# Microcontroller.net
KiCad netlist of a schematic drawn in Altium Designer
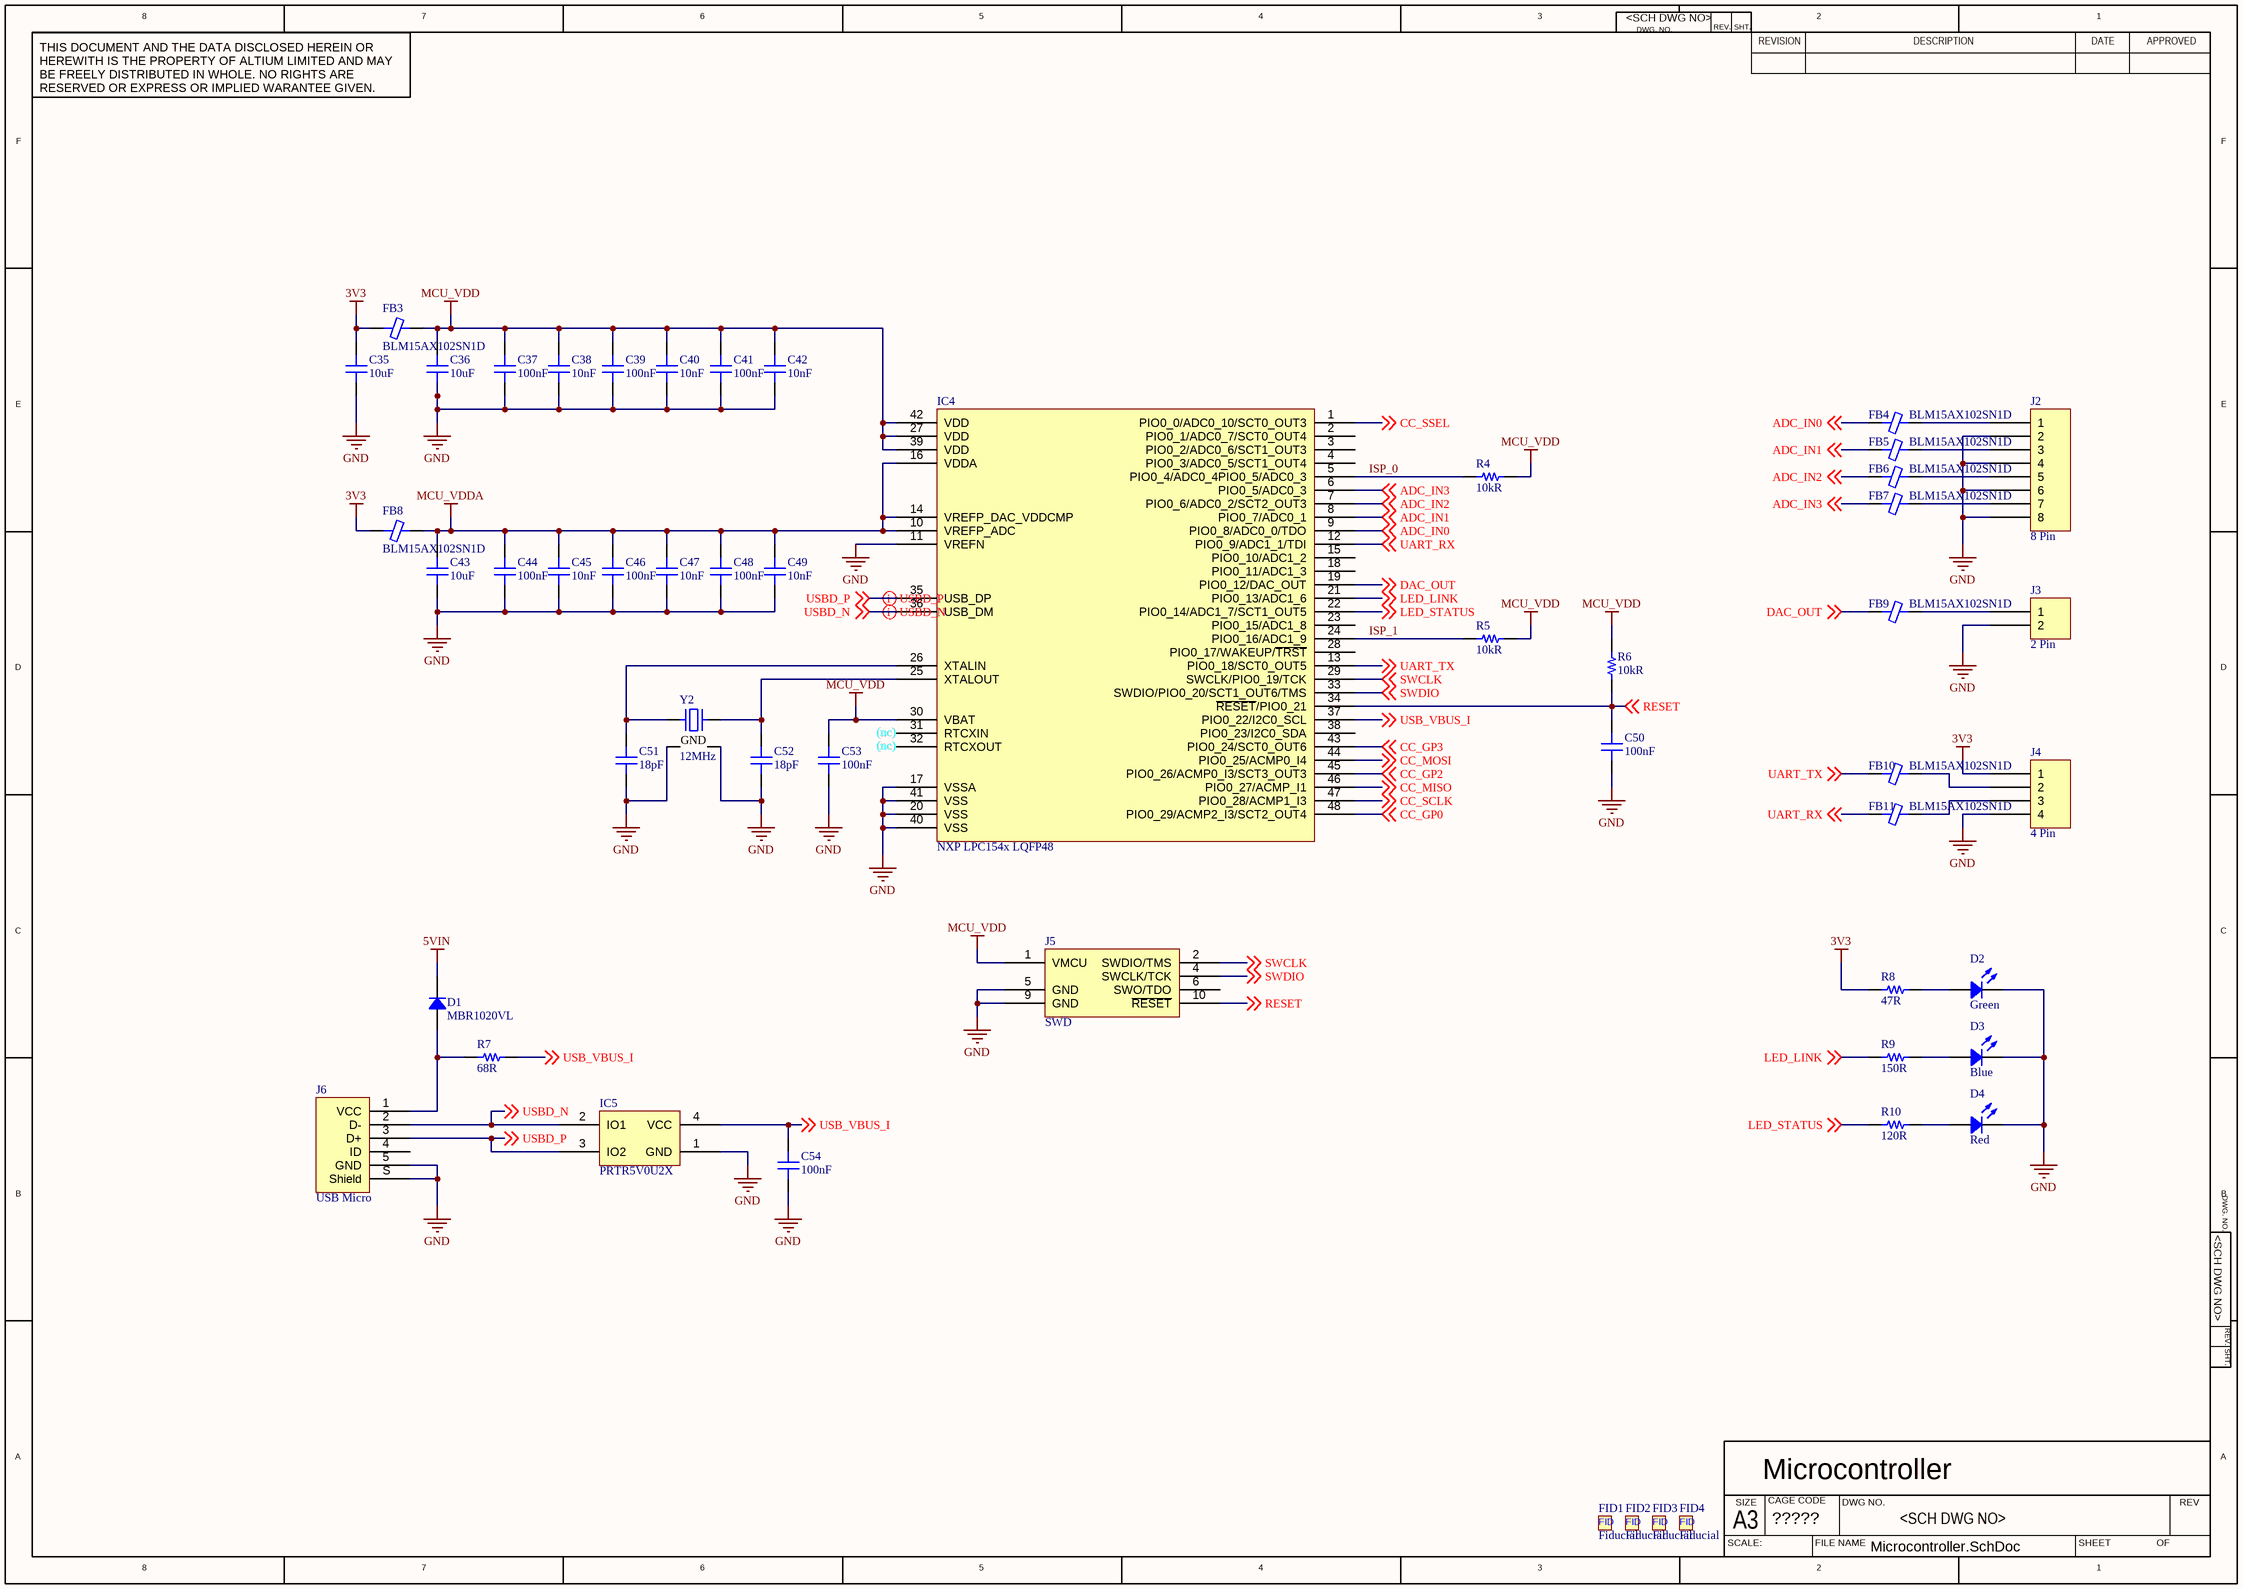
[diagram p0: Microcontroller.SchDoc]

(export (version "E")
  (design (tool "Eeschema 10.0.6"))
  (components
    (comp (ref "C35")
      (value "10uF")
      (footprint "CAP 0805/2012")
      (description "Cap Ceramic 10uF 10V X5R 10% SMD 0805 85C Embossed T/R")
      (fields (field (name "TOLERANCE") "10%") (field (name "VOLTAGE") "10V"))
      (libsource (lib "SCH - PASSIVES - CAPACITOR") (part "Capacitor"))
    )
    (comp (ref "C36")
      (value "10uF")
      (footprint "CAP 0805/2012")
      (description "Cap Ceramic 10uF 10V X5R 10% SMD 0805 85C Embossed T/R")
      (fields (field (name "TOLERANCE") "10%") (field (name "VOLTAGE") "10V"))
      (libsource (lib "SCH - PASSIVES - CAPACITOR") (part "Capacitor"))
    )
    (comp (ref "C37")
      (value "100nF")
      (footprint "CAP 0402/1005")
      (description "Cap Ceramic 0.1uF 10V X5R 20% Pad SMD 0402 85C T/R")
      (fields (field (name "TOLERANCE") "20%"))
      (libsource (lib "SCH - PASSIVES - CAPACITOR") (part "Capacitor"))
    )
    (comp (ref "C38")
      (value "10nF")
      (footprint "CAP 0402/1005")
      (description "TAIYO YUDEN - TMK105B7103KV-F - CERAMIC CAPACITOR 0.01UF, 25V, X7R, 10%, 0402, FULL REEL")
      (fields (field (name "TOLERANCE") "10%") (field (name "VOLTAGE") "25V"))
      (libsource (lib "SCH - PASSIVES - CAPACITOR") (part "Capacitor"))
    )
    (comp (ref "C39")
      (value "100nF")
      (footprint "CAP 0402/1005")
      (description "Cap Ceramic 0.1uF 10V X5R 20% Pad SMD 0402 85C T/R")
      (fields (field (name "TOLERANCE") "20%"))
      (libsource (lib "SCH - PASSIVES - CAPACITOR") (part "Capacitor"))
    )
    (comp (ref "C40")
      (value "10nF")
      (footprint "CAP 0402/1005")
      (description "TAIYO YUDEN - TMK105B7103KV-F - CERAMIC CAPACITOR 0.01UF, 25V, X7R, 10%, 0402, FULL REEL")
      (fields (field (name "TOLERANCE") "10%") (field (name "VOLTAGE") "25V"))
      (libsource (lib "SCH - PASSIVES - CAPACITOR") (part "Capacitor"))
    )
    (comp (ref "C41")
      (value "100nF")
      (footprint "CAP 0402/1005")
      (description "Cap Ceramic 0.1uF 10V X5R 20% Pad SMD 0402 85C T/R")
      (fields (field (name "TOLERANCE") "20%"))
      (libsource (lib "SCH - PASSIVES - CAPACITOR") (part "Capacitor"))
    )
    (comp (ref "C42")
      (value "10nF")
      (footprint "CAP 0402/1005")
      (description "TAIYO YUDEN - TMK105B7103KV-F - CERAMIC CAPACITOR 0.01UF, 25V, X7R, 10%, 0402, FULL REEL")
      (fields (field (name "TOLERANCE") "10%") (field (name "VOLTAGE") "25V"))
      (libsource (lib "SCH - PASSIVES - CAPACITOR") (part "Capacitor"))
    )
    (comp (ref "C43")
      (value "10uF")
      (footprint "CAP 0805/2012")
      (description "Cap Ceramic 10uF 10V X5R 10% SMD 0805 85C Embossed T/R")
      (fields (field (name "TOLERANCE") "10%") (field (name "VOLTAGE") "10V"))
      (libsource (lib "SCH - PASSIVES - CAPACITOR") (part "Capacitor"))
    )
    (comp (ref "C44")
      (value "100nF")
      (footprint "CAP 0402/1005")
      (description "Cap Ceramic 0.1uF 10V X5R 20% Pad SMD 0402 85C T/R")
      (fields (field (name "TOLERANCE") "20%"))
      (libsource (lib "SCH - PASSIVES - CAPACITOR") (part "Capacitor"))
    )
    (comp (ref "C45")
      (value "10nF")
      (footprint "CAP 0402/1005")
      (description "TAIYO YUDEN - TMK105B7103KV-F - CERAMIC CAPACITOR 0.01UF, 25V, X7R, 10%, 0402, FULL REEL")
      (fields (field (name "TOLERANCE") "10%") (field (name "VOLTAGE") "25V"))
      (libsource (lib "SCH - PASSIVES - CAPACITOR") (part "Capacitor"))
    )
    (comp (ref "C46")
      (value "100nF")
      (footprint "CAP 0402/1005")
      (description "Cap Ceramic 0.1uF 10V X5R 20% Pad SMD 0402 85C T/R")
      (fields (field (name "TOLERANCE") "20%"))
      (libsource (lib "SCH - PASSIVES - CAPACITOR") (part "Capacitor"))
    )
    (comp (ref "C47")
      (value "10nF")
      (footprint "CAP 0402/1005")
      (description "TAIYO YUDEN - TMK105B7103KV-F - CERAMIC CAPACITOR 0.01UF, 25V, X7R, 10%, 0402, FULL REEL")
      (fields (field (name "TOLERANCE") "10%") (field (name "VOLTAGE") "25V"))
      (libsource (lib "SCH - PASSIVES - CAPACITOR") (part "Capacitor"))
    )
    (comp (ref "C48")
      (value "100nF")
      (footprint "CAP 0402/1005")
      (description "Cap Ceramic 0.1uF 10V X5R 20% Pad SMD 0402 85C T/R")
      (fields (field (name "TOLERANCE") "20%"))
      (libsource (lib "SCH - PASSIVES - CAPACITOR") (part "Capacitor"))
    )
    (comp (ref "C49")
      (value "10nF")
      (footprint "CAP 0402/1005")
      (description "TAIYO YUDEN - TMK105B7103KV-F - CERAMIC CAPACITOR 0.01UF, 25V, X7R, 10%, 0402, FULL REEL")
      (fields (field (name "TOLERANCE") "10%") (field (name "VOLTAGE") "25V"))
      (libsource (lib "SCH - PASSIVES - CAPACITOR") (part "Capacitor"))
    )
    (comp (ref "C50")
      (value "100nF")
      (footprint "CAP 0402/1005")
      (description "Cap Ceramic 0.1uF 10V X5R 20% Pad SMD 0402 85C T/R")
      (fields (field (name "TOLERANCE") "20%"))
      (libsource (lib "SCH - PASSIVES - CAPACITOR") (part "Capacitor"))
    )
    (comp (ref "C51")
      (value "18pF")
      (footprint "CAP 0402/1005")
      (description "CAP CER 18PF 50V C0G/NPO 0402")
      (fields (field (name "TOLERANCE") "5%") (field (name "VOLTAGE") "50V"))
      (libsource (lib "SCH - PASSIVES - CAPACITOR") (part "Capacitor"))
    )
    (comp (ref "C52")
      (value "18pF")
      (footprint "CAP 0402/1005")
      (description "CAP CER 18PF 50V C0G/NPO 0402")
      (fields (field (name "TOLERANCE") "5%") (field (name "VOLTAGE") "50V"))
      (libsource (lib "SCH - PASSIVES - CAPACITOR") (part "Capacitor"))
    )
    (comp (ref "C53")
      (value "100nF")
      (footprint "CAP 0402/1005")
      (description "Cap Ceramic 0.1uF 10V X5R 20% Pad SMD 0402 85C T/R")
      (fields (field (name "TOLERANCE") "20%"))
      (libsource (lib "SCH - PASSIVES - CAPACITOR") (part "Capacitor"))
    )
    (comp (ref "C54")
      (value "100nF")
      (footprint "CAP 0402/1005")
      (description "Cap Ceramic 0.1uF 10V X5R 20% Pad SMD 0402 85C T/R")
      (fields (field (name "TOLERANCE") "20%"))
      (libsource (lib "SCH - PASSIVES - CAPACITOR") (part "Capacitor"))
    )
    (comp (ref "D1")
      (value "MBR1020VL")
      (footprint "SOD123F")
      (description "DIODE SCHOTTKY 20V 1A SOD123F")
      (libsource (lib "SCH - DIODES - DIODE") (part "Diode"))
    )
    (comp (ref "D2")
      (value "Green")
      (footprint "LED 0603/1608 GREEN")
      (description "0603 green led allngap 571nm-574nm water clear 18-71mcd 130d")
      (libsource (lib "SCH - DIODES - LED") (part "LED"))
    )
    (comp (ref "D3")
      (value "Blue")
      (footprint "LED 0603/1608 BLUE")
      (description "LED Uni-Color Blue 468nm 2-Pin Chip 0603(1608Metric) T/R")
      (libsource (lib "SCH - DIODES - LED") (part "LED"))
    )
    (comp (ref "D4")
      (value "Red")
      (footprint "LED 0603/1608 RED")
      (description "LED RED DIFFUSED 1608 SMD")
      (libsource (lib "SCH - DIODES - LED") (part "LED"))
    )
    (comp (ref "FB3")
      (value "BLM15AX102SN1D")
      (footprint "FER 0402/1005")
      (description "Ferrite Beads Multi-Layer 1KOhm 25% 100MHz 350mA 490mOhm DCR 0402 T/R")
      (fields (field (name "TOLERANCE") "25%"))
      (libsource (lib "SCH - PASSIVES - FERRITE CHIP") (part "Ferrite Chip"))
    )
    (comp (ref "FB4")
      (value "BLM15AX102SN1D")
      (footprint "FER 0402/1005")
      (description "Ferrite Beads Multi-Layer 1KOhm 25% 100MHz 350mA 490mOhm DCR 0402 T/R")
      (fields (field (name "TOLERANCE") "25%"))
      (libsource (lib "SCH - PASSIVES - FERRITE CHIP") (part "Ferrite Chip"))
    )
    (comp (ref "FB5")
      (value "BLM15AX102SN1D")
      (footprint "FER 0402/1005")
      (description "Ferrite Beads Multi-Layer 1KOhm 25% 100MHz 350mA 490mOhm DCR 0402 T/R")
      (fields (field (name "TOLERANCE") "25%"))
      (libsource (lib "SCH - PASSIVES - FERRITE CHIP") (part "Ferrite Chip"))
    )
    (comp (ref "FB6")
      (value "BLM15AX102SN1D")
      (footprint "FER 0402/1005")
      (description "Ferrite Beads Multi-Layer 1KOhm 25% 100MHz 350mA 490mOhm DCR 0402 T/R")
      (fields (field (name "TOLERANCE") "25%"))
      (libsource (lib "SCH - PASSIVES - FERRITE CHIP") (part "Ferrite Chip"))
    )
    (comp (ref "FB7")
      (value "BLM15AX102SN1D")
      (footprint "FER 0402/1005")
      (description "Ferrite Beads Multi-Layer 1KOhm 25% 100MHz 350mA 490mOhm DCR 0402 T/R")
      (fields (field (name "TOLERANCE") "25%"))
      (libsource (lib "SCH - PASSIVES - FERRITE CHIP") (part "Ferrite Chip"))
    )
    (comp (ref "FB8")
      (value "BLM15AX102SN1D")
      (footprint "FER 0402/1005")
      (description "Ferrite Beads Multi-Layer 1KOhm 25% 100MHz 350mA 490mOhm DCR 0402 T/R")
      (fields (field (name "TOLERANCE") "25%"))
      (libsource (lib "SCH - PASSIVES - FERRITE CHIP") (part "Ferrite Chip"))
    )
    (comp (ref "FB9")
      (value "BLM15AX102SN1D")
      (footprint "FER 0402/1005")
      (description "Ferrite Beads Multi-Layer 1KOhm 25% 100MHz 350mA 490mOhm DCR 0402 T/R")
      (fields (field (name "TOLERANCE") "25%"))
      (libsource (lib "SCH - PASSIVES - FERRITE CHIP") (part "Ferrite Chip"))
    )
    (comp (ref "FB10")
      (value "BLM15AX102SN1D")
      (footprint "FER 0402/1005")
      (description "Ferrite Beads Multi-Layer 1KOhm 25% 100MHz 350mA 490mOhm DCR 0402 T/R")
      (fields (field (name "TOLERANCE") "25%"))
      (libsource (lib "SCH - PASSIVES - FERRITE CHIP") (part "Ferrite Chip"))
    )
    (comp (ref "FB11")
      (value "BLM15AX102SN1D")
      (footprint "FER 0402/1005")
      (description "Ferrite Beads Multi-Layer 1KOhm 25% 100MHz 350mA 490mOhm DCR 0402 T/R")
      (fields (field (name "TOLERANCE") "25%"))
      (libsource (lib "SCH - PASSIVES - FERRITE CHIP") (part "Ferrite Chip"))
    )
    (comp (ref "FID1") (value "Fiducial") (footprint "Fiducial") (libsource (lib "Useful") (part "Fiducial")))
    (comp (ref "FID2") (value "Fiducial") (footprint "Fiducial") (libsource (lib "Useful") (part "Fiducial")))
    (comp (ref "FID3") (value "Fiducial") (footprint "Fiducial") (libsource (lib "Useful") (part "Fiducial")))
    (comp (ref "FID4") (value "Fiducial") (footprint "Fiducial") (libsource (lib "Useful") (part "Fiducial")))
    (comp (ref "IC4")
      (value "NXP LPC154x LQFP48")
      (footprint "NXP LQFP-48 7x7mm")
      (description "IC MCU 32BIT 256KB FLASH 48LQFP")
      (libsource (lib "SCH - ARM CORTEX - NXP LPC154X LQFP48") (part "NXP LPC154x LQFP48"))
    )
    (comp (ref "IC5")
      (value "PRTR5V0U2X")
      (footprint "SOT143B")
      (description "TVS DIODE 5.5V SOT143B")
      (libsource (lib "SCH - DIODES - NXP PRTR5V0U2X") (part "NXP PRTR5V0U2X"))
    )
    (comp (ref "J2")
      (value "8 Pin")
      (footprint "FCI 06-381-8PIN")
      (description "TERM BLOCK HDR 8POS 90DEG 3.81MM")
      (libsource (lib "SCH - CONNECTORS - 8 PIN") (part "8 Pin"))
    )
    (comp (ref "J3")
      (value "2 Pin")
      (footprint "FCI 06-381-2PIN")
      (description "TERM BLOCK HDR 2POS 90DEG 3.81MM")
      (libsource (lib "SCH - CONNECTORS - 2 PIN") (part "2 Pin"))
    )
    (comp (ref "J4")
      (value "4 Pin")
      (footprint "FCI 06-381-4PIN")
      (description "TERM BLOCK HDR 4POS 90DEG 3.81MM")
      (libsource (lib "SCH - CONNECTORS - 4 PIN") (part "4 Pin"))
    )
    (comp (ref "J5") (value "SWD") (footprint "10 Pin SWD") (libsource (lib "Useful") (part "SWD")))
    (comp (ref "J6")
      (value "USB Micro")
      (footprint "FCI USB 10118193-0001LF")
      (description "CONN RCPT USB2.0 MICRO B SMD R/A")
      (libsource (lib "SCH - CONNECTORS - USB 2.0 TYPE B MICRO") (part "USB 2.0 Type B Micro"))
    )
    (comp (ref "R4")
      (value "10kR")
      (footprint "RES 0402/1005")
      (description "RES 10K OHM 5% 1/16W 0402")
      (fields (field (name "TOLERANCE") "5%"))
      (libsource (lib "SCH - PASSIVES - RESISTOR") (part "Resistor"))
    )
    (comp (ref "R5")
      (value "10kR")
      (footprint "RES 0402/1005")
      (description "RES 10K OHM 5% 1/16W 0402")
      (fields (field (name "TOLERANCE") "5%"))
      (libsource (lib "SCH - PASSIVES - RESISTOR") (part "Resistor"))
    )
    (comp (ref "R6")
      (value "10kR")
      (footprint "RES 0402/1005")
      (description "RES 10K OHM 5% 1/16W 0402")
      (fields (field (name "TOLERANCE") "5%"))
      (libsource (lib "SCH - PASSIVES - RESISTOR") (part "Resistor"))
    )
    (comp (ref "R7")
      (value "68R")
      (footprint "RES 0402/1005")
      (description "RES SMD 68 OHM 5% 1/16W 0402")
      (fields (field (name "TOLERANCE") "5%"))
      (libsource (lib "SCH - PASSIVES - RESISTOR") (part "Resistor"))
    )
    (comp (ref "R8")
      (value "47R")
      (footprint "RES 0402/1005")
      (description "KOA SPEAR ELECTRONICS - RK73B1JTTD470J - RES, 47R, 5%, 0.1W, 0603, THICK FILM")
      (fields (field (name "TOLERANCE") "5%"))
      (libsource (lib "SCH - PASSIVES - RESISTOR") (part "Resistor"))
    )
    (comp (ref "R9")
      (value "150R")
      (footprint "RES 0402/1005")
      (description "Res Thick Film 0603 150 Ohm 5% 0.1W(1/10W) ±200ppm/C Molded SMD Automotive Punched Paper T/R")
      (fields (field (name "TOLERANCE") "5%"))
      (libsource (lib "SCH - PASSIVES - RESISTOR") (part "Resistor"))
    )
    (comp (ref "R10")
      (value "120R")
      (footprint "RES 0402/1005")
      (fields (field (name "TOLERANCE") "5%"))
      (libsource (lib "SCH - PASSIVES - RESISTOR") (part "Resistor"))
    )
    (comp (ref "Y2")
      (value "12MHz")
      (footprint "ABRACON ABM8G")
      (description "CRYSTAL 12.0000MHZ 18PF SMD")
      (fields (field (name "TOLERANCE") "20ppm"))
      (libsource (lib "SCH - CRYSTALS - ABRACON CRYSTAL ABM8G") (part "Abracon Crystal ABM8G"))
    )
  )
  (nets
    (net (code "1") (name "/ISP_0") (class "Default")
      (node (ref "IC4") (pin "5") (pinfunction "PIO0_4/ADC0_4PIO0_5/ADC0_3_5") (pintype "passive"))
      (node (ref "R4") (pin "2") (pinfunction "2_2") (pintype "passive"))
    )
    (net (code "2") (name "/ISP_1") (class "Default")
      (node (ref "IC4") (pin "24") (pinfunction "PIO0_16/ADC1_9_24") (pintype "passive"))
      (node (ref "R5") (pin "2") (pinfunction "2_2") (pintype "passive"))
    )
    (net (code "3") (name "3V3") (class "Default")
      (node (ref "C35") (pin "2") (pinfunction "2_2") (pintype "passive"))
      (node (ref "FB3") (pin "2") (pinfunction "2_2") (pintype "passive"))
      (node (ref "FB8") (pin "2") (pinfunction "2_2") (pintype "passive"))
      (node (ref "J4") (pin "1") (pinfunction "1_1") (pintype "passive"))
      (node (ref "R8") (pin "1") (pinfunction "1_1") (pintype "passive"))
    )
    (net (code "4") (name "5VIN") (class "Default")
      (node (ref "D1") (pin "2") (pinfunction "2_2") (pintype "passive"))
    )
    (net (code "5") (name "ADC_IN0") (class "Default")
      (node (ref "FB4") (pin "2") (pinfunction "2_2") (pintype "passive"))
      (node (ref "IC4") (pin "9") (pinfunction "PIO0_8/ADC0_0/TDO_9") (pintype "passive"))
    )
    (net (code "6") (name "ADC_IN1") (class "Default")
      (node (ref "FB5") (pin "2") (pinfunction "2_2") (pintype "passive"))
      (node (ref "IC4") (pin "8") (pinfunction "PIO0_7/ADC0_1_8") (pintype "passive"))
    )
    (net (code "7") (name "ADC_IN2") (class "Default")
      (node (ref "FB6") (pin "2") (pinfunction "2_2") (pintype "passive"))
      (node (ref "IC4") (pin "7") (pinfunction "PIO0_6/ADC0_2/SCT2_OUT3_7") (pintype "passive"))
    )
    (net (code "8") (name "ADC_IN3") (class "Default")
      (node (ref "FB7") (pin "2") (pinfunction "2_2") (pintype "passive"))
      (node (ref "IC4") (pin "6") (pinfunction "PIO0_5/ADC0_3_6") (pintype "passive"))
    )
    (net (code "9") (name "CC_GP0") (class "Default")
      (node (ref "IC4") (pin "48") (pinfunction "PIO0_29/ACMP2_I3/SCT2_OUT4_48") (pintype "passive"))
    )
    (net (code "10") (name "CC_GP2") (class "Default")
      (node (ref "IC4") (pin "45") (pinfunction "PIO0_26/ACMP0_I3/SCT3_OUT3_45") (pintype "passive"))
    )
    (net (code "11") (name "CC_GP3") (class "Default")
      (node (ref "IC4") (pin "43") (pinfunction "PIO0_24/SCT0_OUT6_43") (pintype "passive"))
    )
    (net (code "12") (name "CC_MISO") (class "Default")
      (node (ref "IC4") (pin "46") (pinfunction "PIO0_27/ACMP_I1_46") (pintype "passive"))
    )
    (net (code "13") (name "CC_MOSI") (class "Default")
      (node (ref "IC4") (pin "44") (pinfunction "PIO0_25/ACMP0_I4_44") (pintype "passive"))
    )
    (net (code "14") (name "CC_SCLK") (class "Default")
      (node (ref "IC4") (pin "47") (pinfunction "PIO0_28/ACMP1_I3_47") (pintype "passive"))
    )
    (net (code "15") (name "CC_SSEL") (class "Default")
      (node (ref "IC4") (pin "1") (pinfunction "PIO0_0/ADC0_10/SCT0_OUT3_1") (pintype "passive"))
    )
    (net (code "16") (name "DAC_OUT") (class "Default")
      (node (ref "FB9") (pin "2") (pinfunction "2_2") (pintype "passive"))
      (node (ref "IC4") (pin "19") (pinfunction "PIO0_12/DAC_OUT_19") (pintype "passive"))
    )
    (net (code "17") (name "GND") (class "Default")
      (node (ref "C35") (pin "1") (pinfunction "1_1") (pintype "passive"))
      (node (ref "C36") (pin "1") (pinfunction "1_1") (pintype "passive"))
      (node (ref "C37") (pin "1") (pinfunction "1_1") (pintype "passive"))
      (node (ref "C38") (pin "1") (pinfunction "1_1") (pintype "passive"))
      (node (ref "C39") (pin "1") (pinfunction "1_1") (pintype "passive"))
      (node (ref "C40") (pin "1") (pinfunction "1_1") (pintype "passive"))
      (node (ref "C41") (pin "1") (pinfunction "1_1") (pintype "passive"))
      (node (ref "C42") (pin "1") (pinfunction "1_1") (pintype "passive"))
      (node (ref "C43") (pin "1") (pinfunction "1_1") (pintype "passive"))
      (node (ref "C44") (pin "1") (pinfunction "1_1") (pintype "passive"))
      (node (ref "C45") (pin "1") (pinfunction "1_1") (pintype "passive"))
      (node (ref "C46") (pin "1") (pinfunction "1_1") (pintype "passive"))
      (node (ref "C47") (pin "1") (pinfunction "1_1") (pintype "passive"))
      (node (ref "C48") (pin "1") (pinfunction "1_1") (pintype "passive"))
      (node (ref "C49") (pin "1") (pinfunction "1_1") (pintype "passive"))
      (node (ref "C50") (pin "1") (pinfunction "1_1") (pintype "passive"))
      (node (ref "C51") (pin "1") (pinfunction "1_1") (pintype "passive"))
      (node (ref "C52") (pin "1") (pinfunction "1_1") (pintype "passive"))
      (node (ref "C53") (pin "1") (pinfunction "1_1") (pintype "passive"))
      (node (ref "C54") (pin "1") (pinfunction "1_1") (pintype "passive"))
      (node (ref "D2") (pin "2") (pinfunction "2_2") (pintype "passive"))
      (node (ref "D3") (pin "2") (pinfunction "2_2") (pintype "passive"))
      (node (ref "D4") (pin "2") (pinfunction "2_2") (pintype "passive"))
      (node (ref "IC4") (pin "11") (pinfunction "VREFN_11") (pintype "passive"))
      (node (ref "IC4") (pin "17") (pinfunction "VSSA_17") (pintype "passive"))
      (node (ref "IC4") (pin "20") (pinfunction "VSS_20") (pintype "passive"))
      (node (ref "IC4") (pin "40") (pinfunction "VSS_40") (pintype "passive"))
      (node (ref "IC4") (pin "41") (pinfunction "VSS_41") (pintype "passive"))
      (node (ref "IC5") (pin "1") (pinfunction "GND_1") (pintype "passive"))
      (node (ref "J2") (pin "2") (pinfunction "2_2") (pintype "passive"))
      (node (ref "J2") (pin "4") (pinfunction "4_4") (pintype "passive"))
      (node (ref "J2") (pin "6") (pinfunction "6_6") (pintype "passive"))
      (node (ref "J2") (pin "8") (pinfunction "8_8") (pintype "passive"))
      (node (ref "J3") (pin "2") (pinfunction "2_2") (pintype "passive"))
      (node (ref "J4") (pin "4") (pinfunction "4_4") (pintype "passive"))
      (node (ref "J5") (pin "5") (pinfunction "GND_5") (pintype "passive"))
      (node (ref "J5") (pin "9") (pinfunction "GND_9") (pintype "passive"))
      (node (ref "J6") (pin "5") (pinfunction "GND_5") (pintype "passive"))
      (node (ref "J6") (pin "S") (pinfunction "Shield_S") (pintype "passive"))
      (node (ref "Y2") (pin "2") (pinfunction "GND_2") (pintype "passive"))
      (node (ref "Y2") (pin "4") (pinfunction "GND_4") (pintype "passive"))
    )
    (net (code "18") (name "LED_LINK") (class "Default")
      (node (ref "IC4") (pin "21") (pinfunction "PIO0_13/ADC1_6_21") (pintype "passive"))
      (node (ref "R9") (pin "1") (pinfunction "1_1") (pintype "passive"))
    )
    (net (code "19") (name "LED_STATUS") (class "Default")
      (node (ref "IC4") (pin "22") (pinfunction "PIO0_14/ADC1_7/SCT1_OUT5_22") (pintype "passive"))
      (node (ref "R10") (pin "1") (pinfunction "1_1") (pintype "passive"))
    )
    (net (code "20") (name "MCU_VDD") (class "Default")
      (node (ref "C36") (pin "2") (pinfunction "2_2") (pintype "passive"))
      (node (ref "C37") (pin "2") (pinfunction "2_2") (pintype "passive"))
      (node (ref "C38") (pin "2") (pinfunction "2_2") (pintype "passive"))
      (node (ref "C39") (pin "2") (pinfunction "2_2") (pintype "passive"))
      (node (ref "C40") (pin "2") (pinfunction "2_2") (pintype "passive"))
      (node (ref "C41") (pin "2") (pinfunction "2_2") (pintype "passive"))
      (node (ref "C42") (pin "2") (pinfunction "2_2") (pintype "passive"))
      (node (ref "C53") (pin "2") (pinfunction "2_2") (pintype "passive"))
      (node (ref "FB3") (pin "1") (pinfunction "1_1") (pintype "passive"))
      (node (ref "IC4") (pin "27") (pinfunction "VDD_27") (pintype "passive"))
      (node (ref "IC4") (pin "30") (pinfunction "VBAT_30") (pintype "passive"))
      (node (ref "IC4") (pin "39") (pinfunction "VDD_39") (pintype "passive"))
      (node (ref "IC4") (pin "42") (pinfunction "VDD_42") (pintype "passive"))
      (node (ref "J5") (pin "1") (pinfunction "VMCU_1") (pintype "passive"))
      (node (ref "R4") (pin "1") (pinfunction "1_1") (pintype "passive"))
      (node (ref "R5") (pin "1") (pinfunction "1_1") (pintype "passive"))
      (node (ref "R6") (pin "1") (pinfunction "1_1") (pintype "passive"))
    )
    (net (code "21") (name "MCU_VDDA") (class "Default")
      (node (ref "C43") (pin "2") (pinfunction "2_2") (pintype "passive"))
      (node (ref "C44") (pin "2") (pinfunction "2_2") (pintype "passive"))
      (node (ref "C45") (pin "2") (pinfunction "2_2") (pintype "passive"))
      (node (ref "C46") (pin "2") (pinfunction "2_2") (pintype "passive"))
      (node (ref "C47") (pin "2") (pinfunction "2_2") (pintype "passive"))
      (node (ref "C48") (pin "2") (pinfunction "2_2") (pintype "passive"))
      (node (ref "C49") (pin "2") (pinfunction "2_2") (pintype "passive"))
      (node (ref "FB8") (pin "1") (pinfunction "1_1") (pintype "passive"))
      (node (ref "IC4") (pin "10") (pinfunction "VREFP_ADC_10") (pintype "passive"))
      (node (ref "IC4") (pin "14") (pinfunction "VREFP_DAC_VDDCMP_14") (pintype "passive"))
      (node (ref "IC4") (pin "16") (pinfunction "VDDA_16") (pintype "passive"))
    )
    (net (code "22") (name "Net-(D2-Pad1)") (class "Default")
      (node (ref "D2") (pin "1") (pinfunction "1_1") (pintype "passive"))
      (node (ref "R8") (pin "2") (pinfunction "2_2") (pintype "passive"))
    )
    (net (code "23") (name "Net-(D3-Pad1)") (class "Default")
      (node (ref "D3") (pin "1") (pinfunction "1_1") (pintype "passive"))
      (node (ref "R9") (pin "2") (pinfunction "2_2") (pintype "passive"))
    )
    (net (code "24") (name "Net-(D4-Pad1)") (class "Default")
      (node (ref "D4") (pin "1") (pinfunction "1_1") (pintype "passive"))
      (node (ref "R10") (pin "2") (pinfunction "2_2") (pintype "passive"))
    )
    (net (code "25") (name "Net-(FB4-Pad1)") (class "Default")
      (node (ref "FB4") (pin "1") (pinfunction "1_1") (pintype "passive"))
      (node (ref "J2") (pin "1") (pinfunction "1_1") (pintype "passive"))
    )
    (net (code "26") (name "Net-(FB5-Pad1)") (class "Default")
      (node (ref "FB5") (pin "1") (pinfunction "1_1") (pintype "passive"))
      (node (ref "J2") (pin "3") (pinfunction "3_3") (pintype "passive"))
    )
    (net (code "27") (name "Net-(FB6-Pad1)") (class "Default")
      (node (ref "FB6") (pin "1") (pinfunction "1_1") (pintype "passive"))
      (node (ref "J2") (pin "5") (pinfunction "5_5") (pintype "passive"))
    )
    (net (code "28") (name "Net-(FB7-Pad1)") (class "Default")
      (node (ref "FB7") (pin "1") (pinfunction "1_1") (pintype "passive"))
      (node (ref "J2") (pin "7") (pinfunction "7_7") (pintype "passive"))
    )
    (net (code "29") (name "Net-(FB9-Pad1)") (class "Default")
      (node (ref "FB9") (pin "1") (pinfunction "1_1") (pintype "passive"))
      (node (ref "J3") (pin "1") (pinfunction "1_1") (pintype "passive"))
    )
    (net (code "30") (name "Net-(FB10-Pad1)") (class "Default")
      (node (ref "FB10") (pin "1") (pinfunction "1_1") (pintype "passive"))
      (node (ref "J4") (pin "2") (pinfunction "2_2") (pintype "passive"))
    )
    (net (code "31") (name "Net-(FB11-Pad1)") (class "Default")
      (node (ref "FB11") (pin "1") (pinfunction "1_1") (pintype "passive"))
      (node (ref "J4") (pin "3") (pinfunction "3_3") (pintype "passive"))
    )
    (net (code "32") (name "Net-(IC4-XTALIN)") (class "Default")
      (node (ref "C51") (pin "2") (pinfunction "2_2") (pintype "passive"))
      (node (ref "IC4") (pin "26") (pinfunction "XTALIN_26") (pintype "passive"))
      (node (ref "Y2") (pin "1") (pinfunction "1_1") (pintype "passive"))
    )
    (net (code "33") (name "Net-(IC4-XTALOUT)") (class "Default")
      (node (ref "C52") (pin "2") (pinfunction "2_2") (pintype "passive"))
      (node (ref "IC4") (pin "25") (pinfunction "XTALOUT_25") (pintype "passive"))
      (node (ref "Y2") (pin "3") (pinfunction "3_3") (pintype "passive"))
    )
    (net (code "34") (name "Net-(J6-VCC)") (class "Default")
      (node (ref "D1") (pin "1") (pinfunction "1_1") (pintype "passive"))
      (node (ref "J6") (pin "1") (pinfunction "VCC_1") (pintype "passive"))
      (node (ref "R7") (pin "2") (pinfunction "2_2") (pintype "passive"))
    )
    (net (code "35") (name "RESET") (class "Default")
      (node (ref "C50") (pin "2") (pinfunction "2_2") (pintype "passive"))
      (node (ref "IC4") (pin "34") (pinfunction "~{RESET}/PIO0_21_34") (pintype "passive"))
      (node (ref "J5") (pin "10") (pinfunction "~{RESET}_10") (pintype "passive"))
      (node (ref "R6") (pin "2") (pinfunction "2_2") (pintype "passive"))
    )
    (net (code "36") (name "SWCLK") (class "Default")
      (node (ref "IC4") (pin "29") (pinfunction "SWCLK/PIO0_19/TCK_29") (pintype "passive"))
      (node (ref "J5") (pin "2") (pinfunction "SWDIO/TMS_2") (pintype "passive"))
    )
    (net (code "37") (name "SWDIO") (class "Default")
      (node (ref "IC4") (pin "33") (pinfunction "SWDIO/PIO0_20/SCT1_OUT6/TMS_33") (pintype "passive"))
      (node (ref "J5") (pin "4") (pinfunction "SWCLK/TCK_4") (pintype "passive"))
    )
    (net (code "38") (name "UART_RX") (class "Default")
      (node (ref "FB11") (pin "2") (pinfunction "2_2") (pintype "passive"))
      (node (ref "IC4") (pin "12") (pinfunction "PIO0_9/ADC1_1/TDI_12") (pintype "passive"))
    )
    (net (code "39") (name "UART_TX") (class "Default")
      (node (ref "FB10") (pin "2") (pinfunction "2_2") (pintype "passive"))
      (node (ref "IC4") (pin "13") (pinfunction "PIO0_18/SCT0_OUT5_13") (pintype "passive"))
    )
    (net (code "40") (name "USBD_N") (class "Default")
      (node (ref "IC4") (pin "36") (pinfunction "USB_DM_36") (pintype "passive"))
      (node (ref "IC5") (pin "2") (pinfunction "IO1_2") (pintype "passive"))
      (node (ref "J6") (pin "2") (pinfunction "D-_2") (pintype "passive"))
    )
    (net (code "41") (name "USBD_P") (class "Default")
      (node (ref "IC4") (pin "35") (pinfunction "USB_DP_35") (pintype "passive"))
      (node (ref "IC5") (pin "3") (pinfunction "IO2_3") (pintype "passive"))
      (node (ref "J6") (pin "3") (pinfunction "D+_3") (pintype "passive"))
    )
    (net (code "42") (name "USB_VBUS_I") (class "Default")
      (node (ref "C54") (pin "2") (pinfunction "2_2") (pintype "passive"))
      (node (ref "IC4") (pin "37") (pinfunction "PIO0_22/I2C0_SCL_37") (pintype "passive"))
      (node (ref "IC5") (pin "4") (pinfunction "VCC_4") (pintype "passive"))
      (node (ref "R7") (pin "1") (pinfunction "1_1") (pintype "passive"))
    )
    (net (code "43") (name "unconnected-(IC4-PIO0_1{slash}ADC0_7{slash}SCT0_OUT4-Pad2)") (class "Default")
      (node (ref "IC4") (pin "2") (pinfunction "PIO0_1/ADC0_7/SCT0_OUT4_2") (pintype "passive"))
    )
    (net (code "44") (name "unconnected-(IC4-PIO0_2{slash}ADC0_6{slash}SCT1_OUT3-Pad3)") (class "Default")
      (node (ref "IC4") (pin "3") (pinfunction "PIO0_2/ADC0_6/SCT1_OUT3_3") (pintype "passive"))
    )
    (net (code "45") (name "unconnected-(IC4-PIO0_3{slash}ADC0_5{slash}SCT1_OUT4-Pad4)") (class "Default")
      (node (ref "IC4") (pin "4") (pinfunction "PIO0_3/ADC0_5/SCT1_OUT4_4") (pintype "passive"))
    )
    (net (code "46") (name "unconnected-(IC4-PIO0_10{slash}ADC1_2-Pad15)") (class "Default")
      (node (ref "IC4") (pin "15") (pinfunction "PIO0_10/ADC1_2_15") (pintype "passive"))
    )
    (net (code "47") (name "unconnected-(IC4-PIO0_11{slash}ADC1_3-Pad18)") (class "Default")
      (node (ref "IC4") (pin "18") (pinfunction "PIO0_11/ADC1_3_18") (pintype "passive"))
    )
    (net (code "48") (name "unconnected-(IC4-PIO0_15{slash}ADC1_8-Pad23)") (class "Default")
      (node (ref "IC4") (pin "23") (pinfunction "PIO0_15/ADC1_8_23") (pintype "passive"))
    )
    (net (code "49") (name "unconnected-(IC4-PIO0_17{slash}WAKEUP{slash}~{TRST}-Pad28)") (class "Default")
      (node (ref "IC4") (pin "28") (pinfunction "PIO0_17/WAKEUP/~{TRST}_28") (pintype "passive"))
    )
    (net (code "50") (name "unconnected-(IC4-PIO0_23{slash}I2C0_SDA-Pad38)") (class "Default")
      (node (ref "IC4") (pin "38") (pinfunction "PIO0_23/I2C0_SDA_38") (pintype "passive"))
    )
    (net (code "51") (name "unconnected-(IC4-RTCXIN-Pad31)") (class "Default")
      (node (ref "IC4") (pin "31") (pinfunction "RTCXIN_31") (pintype "passive"))
    )
    (net (code "52") (name "unconnected-(IC4-RTCXOUT-Pad32)") (class "Default")
      (node (ref "IC4") (pin "32") (pinfunction "RTCXOUT_32") (pintype "passive"))
    )
    (net (code "53") (name "unconnected-(J5-SWO{slash}TDO-Pad6)") (class "Default")
      (node (ref "J5") (pin "6") (pinfunction "SWO/TDO_6") (pintype "passive"))
    )
    (net (code "54") (name "unconnected-(J6-ID-Pad4)") (class "Default")
      (node (ref "J6") (pin "4") (pinfunction "ID_4") (pintype "passive"))
    )
  )
)
